# Power.net
KiCad netlist of a schematic drawn in Altium Designer
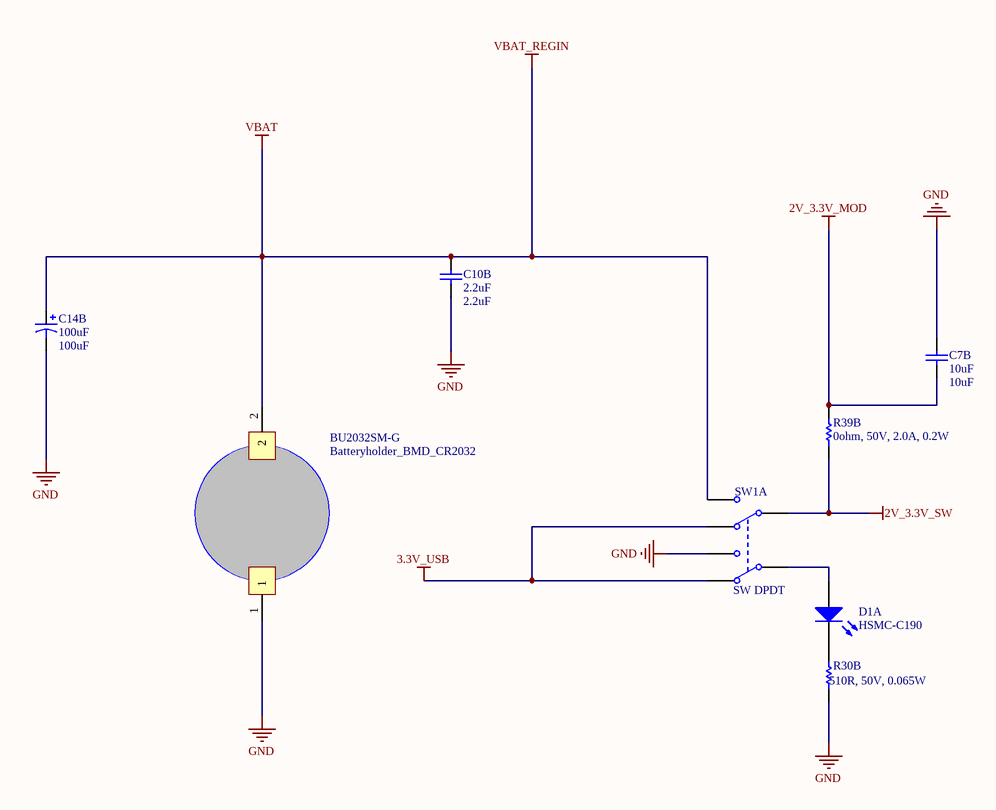
[diagram p0: Power.SchDoc]

(export (version "E")
  (design (tool "Eeschema 10.0.6"))
  (components
    (comp (ref "BU2032SM-G")
      (value "Batteryholder_BMD_CR2032")
      (footprint "DKB113:Batteryholder_BMD_CR2032")
      (libsource (lib "DKB113") (part "Batteryholder_BMD_CR2032"))
    )
    (comp (ref "C7B")
      (value "10uF")
      (footprint "C0805")
      (description "Capacitor (Semiconductor SIM Model)")
      (fields (field (name "ALTIUM_VALUE") "10uF") (field (name "PUBLISHER") "Altium Limited"))
      (libsource (lib "Miscellaneous Devices") (part "Cap Semi"))
    )
    (comp (ref "C10B")
      (value "2.2uF")
      (footprint "C0805")
      (description "Capacitor (Semiconductor SIM Model)")
      (fields (field (name "ALTIUM_VALUE") "2.2uF") (field (name "PUBLISHER") "Altium Limited"))
      (libsource (lib "Miscellaneous Devices") (part "Cap Semi"))
    )
    (comp (ref "C14B")
      (value "100uF")
      (footprint "C0805")
      (description "Polarized Capacitor (Surface Mount)")
      (fields (field (name "ALTIUM_VALUE") "100uF") (field (name "PUBLISHER") "Altium Limited"))
      (libsource (lib "Miscellaneous Devices") (part "Cap Pol3"))
    )
    (comp (ref "D1A")
      (value "HSMC-C190")
      (footprint "1.6X0.8X0.8")
      (description "High Performance Chip LED, Red")
      (fields (field (name "PUBLISHER") "Altium Limited"))
      (libsource (lib "Agilent Optoelectronic LED") (part "HSMC-C190"))
    )
    (comp (ref "R30B")
      (value "510R, 50V, 0.065W")
      (footprint "ERA-0805")
      (fields (field (name "PUBLISHER") "Altium Limited"))
      (libsource (lib "Panasonic Resistor") (part "ERAS"))
    )
    (comp (ref "R39B")
      (value "0ohm, 50V, 2.0A, 0.2W")
      (footprint "ERA-0805")
      (fields (field (name "PUBLISHER") "Altium Limited"))
      (libsource (lib "Panasonic Resistor") (part "ERAS"))
    )
    (comp (ref "SW1A")
      (value "SW DPDT")
      (footprint "TM4C_Launchpad:JS202011SCQN")
      (description "Switch")
      (fields (field (name "PUBLISHER") "Altium Limited"))
      (libsource (lib "Miscellaneous Devices") (part "SW DPDT"))
    )
  )
  (nets
    (net (code "1") (name "2V_3.3V_MOD") (class "Default")
      (node (ref "C7B") (pin "1") (pinfunction "1_1") (pintype "passive"))
      (node (ref "R39B") (pin "2") (pinfunction "2_2") (pintype "passive"))
    )
    (net (code "2") (name "2V_3.3V_SW") (class "Default")
      (node (ref "R39B") (pin "1") (pinfunction "1_1") (pintype "passive"))
      (node (ref "SW1A") (pin "5") (pinfunction "COMMON2_5") (pintype "passive"))
    )
    (net (code "3") (name "3.3V_USB") (class "Default")
      (node (ref "SW1A") (pin "2") (pinfunction "NC1_2") (pintype "passive"))
      (node (ref "SW1A") (pin "4") (pinfunction "NC2_4") (pintype "passive"))
    )
    (net (code "4") (name "GND") (class "Default")
      (node (ref "BU2032SM-G") (pin "1") (pinfunction "1_1") (pintype "passive"))
      (node (ref "C10B") (pin "1") (pinfunction "1_1") (pintype "passive"))
      (node (ref "C14B") (pin "2") (pinfunction "2_2") (pintype "passive"))
      (node (ref "C7B") (pin "2") (pinfunction "2_2") (pintype "passive"))
      (node (ref "R30B") (pin "1") (pinfunction "1_1") (pintype "passive"))
      (node (ref "SW1A") (pin "3") (pinfunction "NO1_3") (pintype "passive"))
    )
    (net (code "5") (name "Net-(D1A-A)") (class "Default")
      (node (ref "D1A") (pin "1") (pinfunction "A_1") (pintype "passive"))
      (node (ref "SW1A") (pin "1") (pinfunction "COMMON1_1") (pintype "passive"))
    )
    (net (code "6") (name "Net-(D1A-K)") (class "Default")
      (node (ref "D1A") (pin "2") (pinfunction "K_2") (pintype "passive"))
      (node (ref "R30B") (pin "2") (pinfunction "2_2") (pintype "passive"))
    )
    (net (code "7") (name "VBAT") (class "Default")
      (node (ref "BU2032SM-G") (pin "2") (pinfunction "2_2") (pintype "passive"))
      (node (ref "C10B") (pin "2") (pinfunction "2_2") (pintype "passive"))
      (node (ref "C14B") (pin "1") (pinfunction "1_1") (pintype "passive"))
      (node (ref "SW1A") (pin "6") (pinfunction "NO2_6") (pintype "passive"))
    )
  )
)
